# 0231-carrier-dcdc-3a.net
KiCad netlist of a schematic drawn in EAGLE
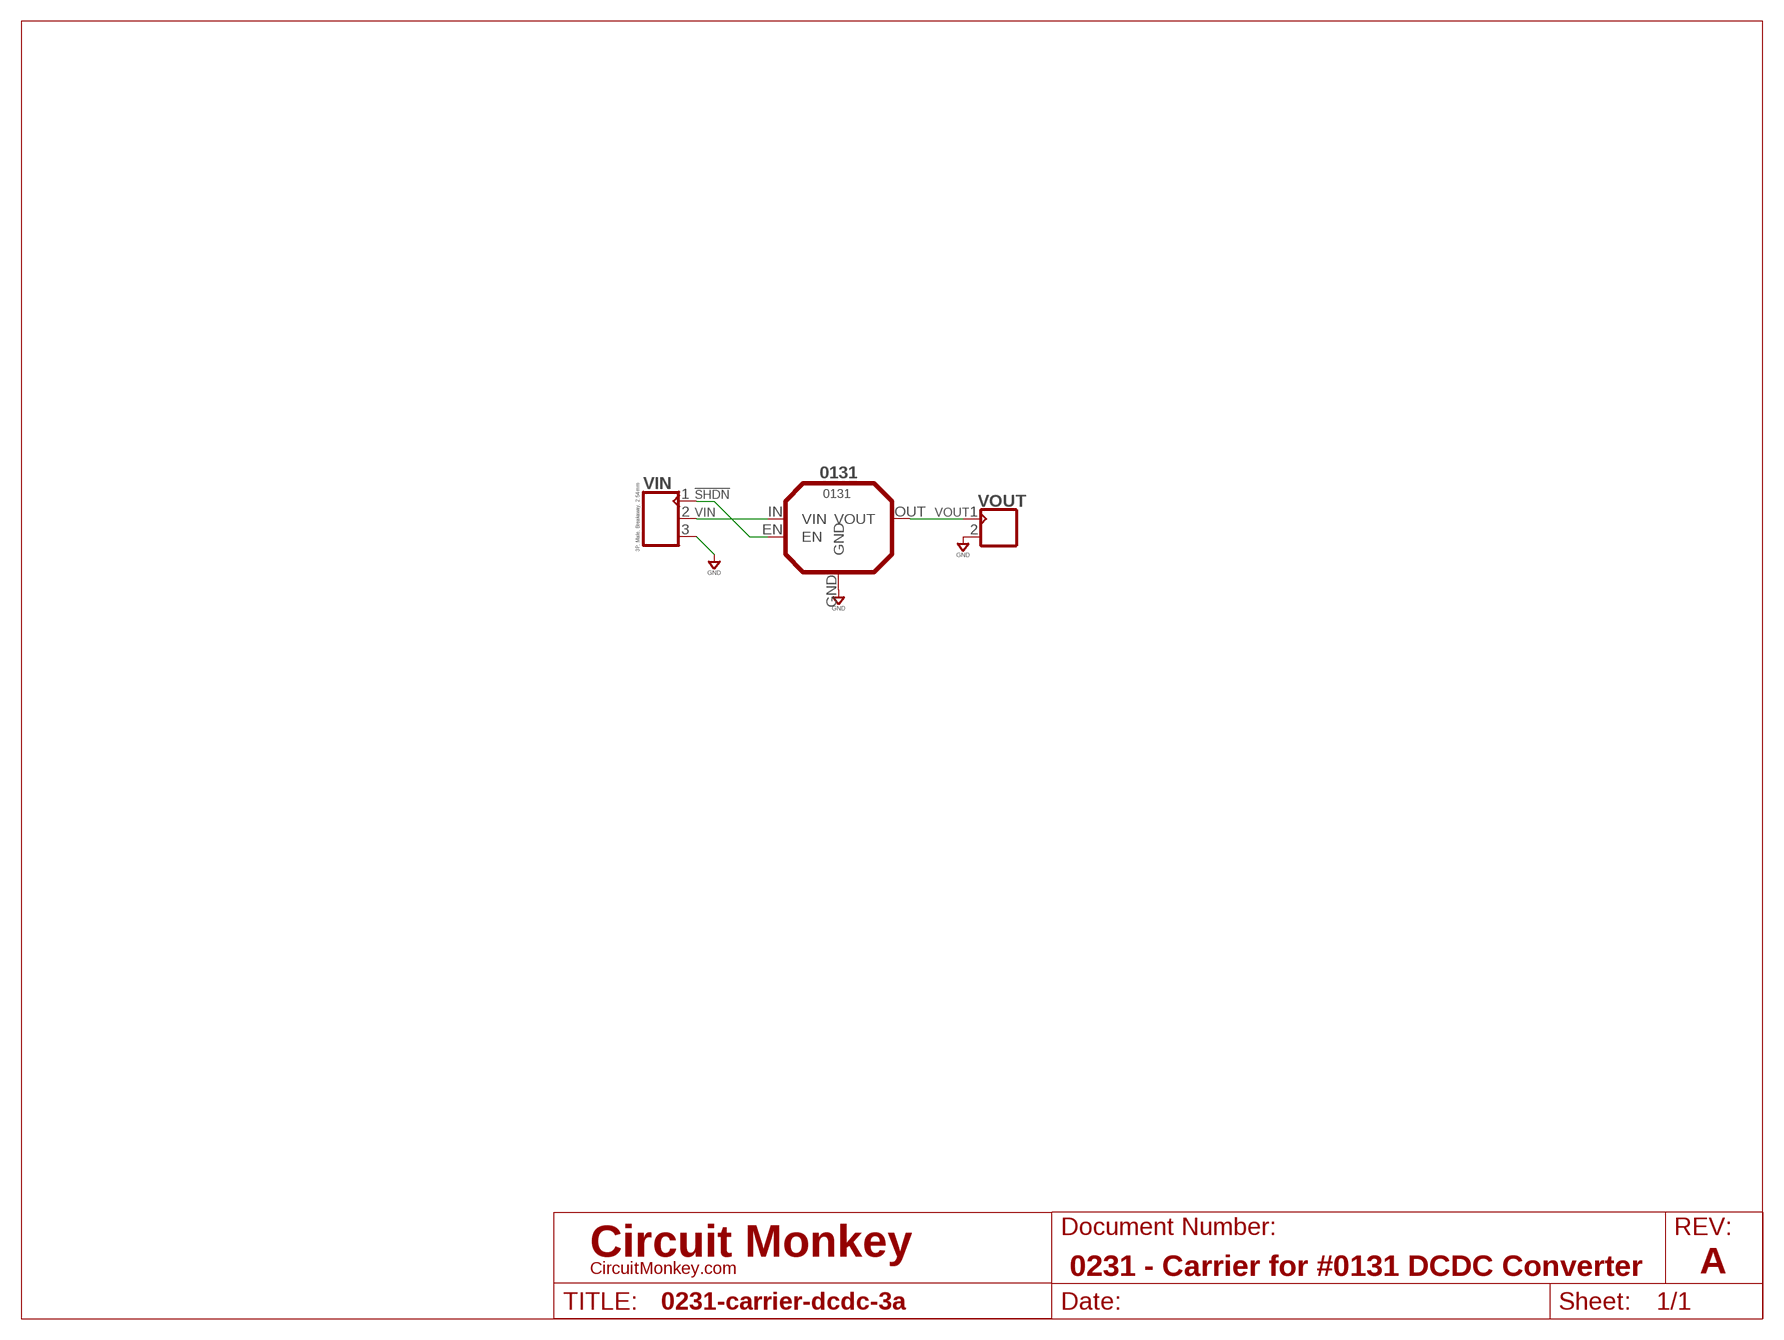
[diagram p0: schematic, sheet 1]

(export (version "E")
  (design (tool "Eeschema 10.0.6"))
  (components
    (comp (ref "0131")
      (value "0131")
      (footprint "eagle-import:0131A")
      (fields (field (name "MFR") "Circuit Monkey"))
      (libsource (lib "eagle-import") (part "0131REV-A"))
    )
    (comp (ref "VIN")
      (value "3P, Male, Breakaway, 2.54mm")
      (footprint "eagle-import:MA03X1-VT-THD")
      (libsource (lib "eagle-import") (part "CON_03X1-2.54MM-THD-VT"))
    )
    (comp (ref "VOUT")
      (value "CON_02X1-2.54MM-THD-VT")
      (footprint "eagle-import:MA02X1-VT-THD")
      (libsource (lib "eagle-import") (part "CON_02X1-2.54MM-THD-VT"))
    )
  )
  (nets
    (net (code "1") (name "/VIN") (class "Default")
      (node (ref "0131") (pin "IN") (pinfunction "VIN_IN") (pintype "bidirectional"))
      (node (ref "VIN") (pin "2") (pinfunction "2_2") (pintype "passive"))
    )
    (net (code "2") (name "/VOUT") (class "Default")
      (node (ref "0131") (pin "OUT") (pinfunction "VOUT_OUT") (pintype "bidirectional"))
      (node (ref "VOUT") (pin "1") (pinfunction "1_1") (pintype "passive"))
    )
    (net (code "3") (name "/~{SHDN}") (class "Default")
      (node (ref "0131") (pin "EN") (pinfunction "EN_EN") (pintype "bidirectional"))
      (node (ref "VIN") (pin "1") (pinfunction "1_1") (pintype "passive"))
    )
    (net (code "4") (name "GND") (class "Default")
      (node (ref "0131") (pin "GND") (pinfunction "GND_GND") (pintype "bidirectional"))
      (node (ref "VIN") (pin "3") (pinfunction "3_3") (pintype "passive"))
      (node (ref "VOUT") (pin "2") (pinfunction "2_2") (pintype "passive"))
    )
  )
)
